# Sheet1.net
KiCad netlist of a schematic drawn in Altium Designer
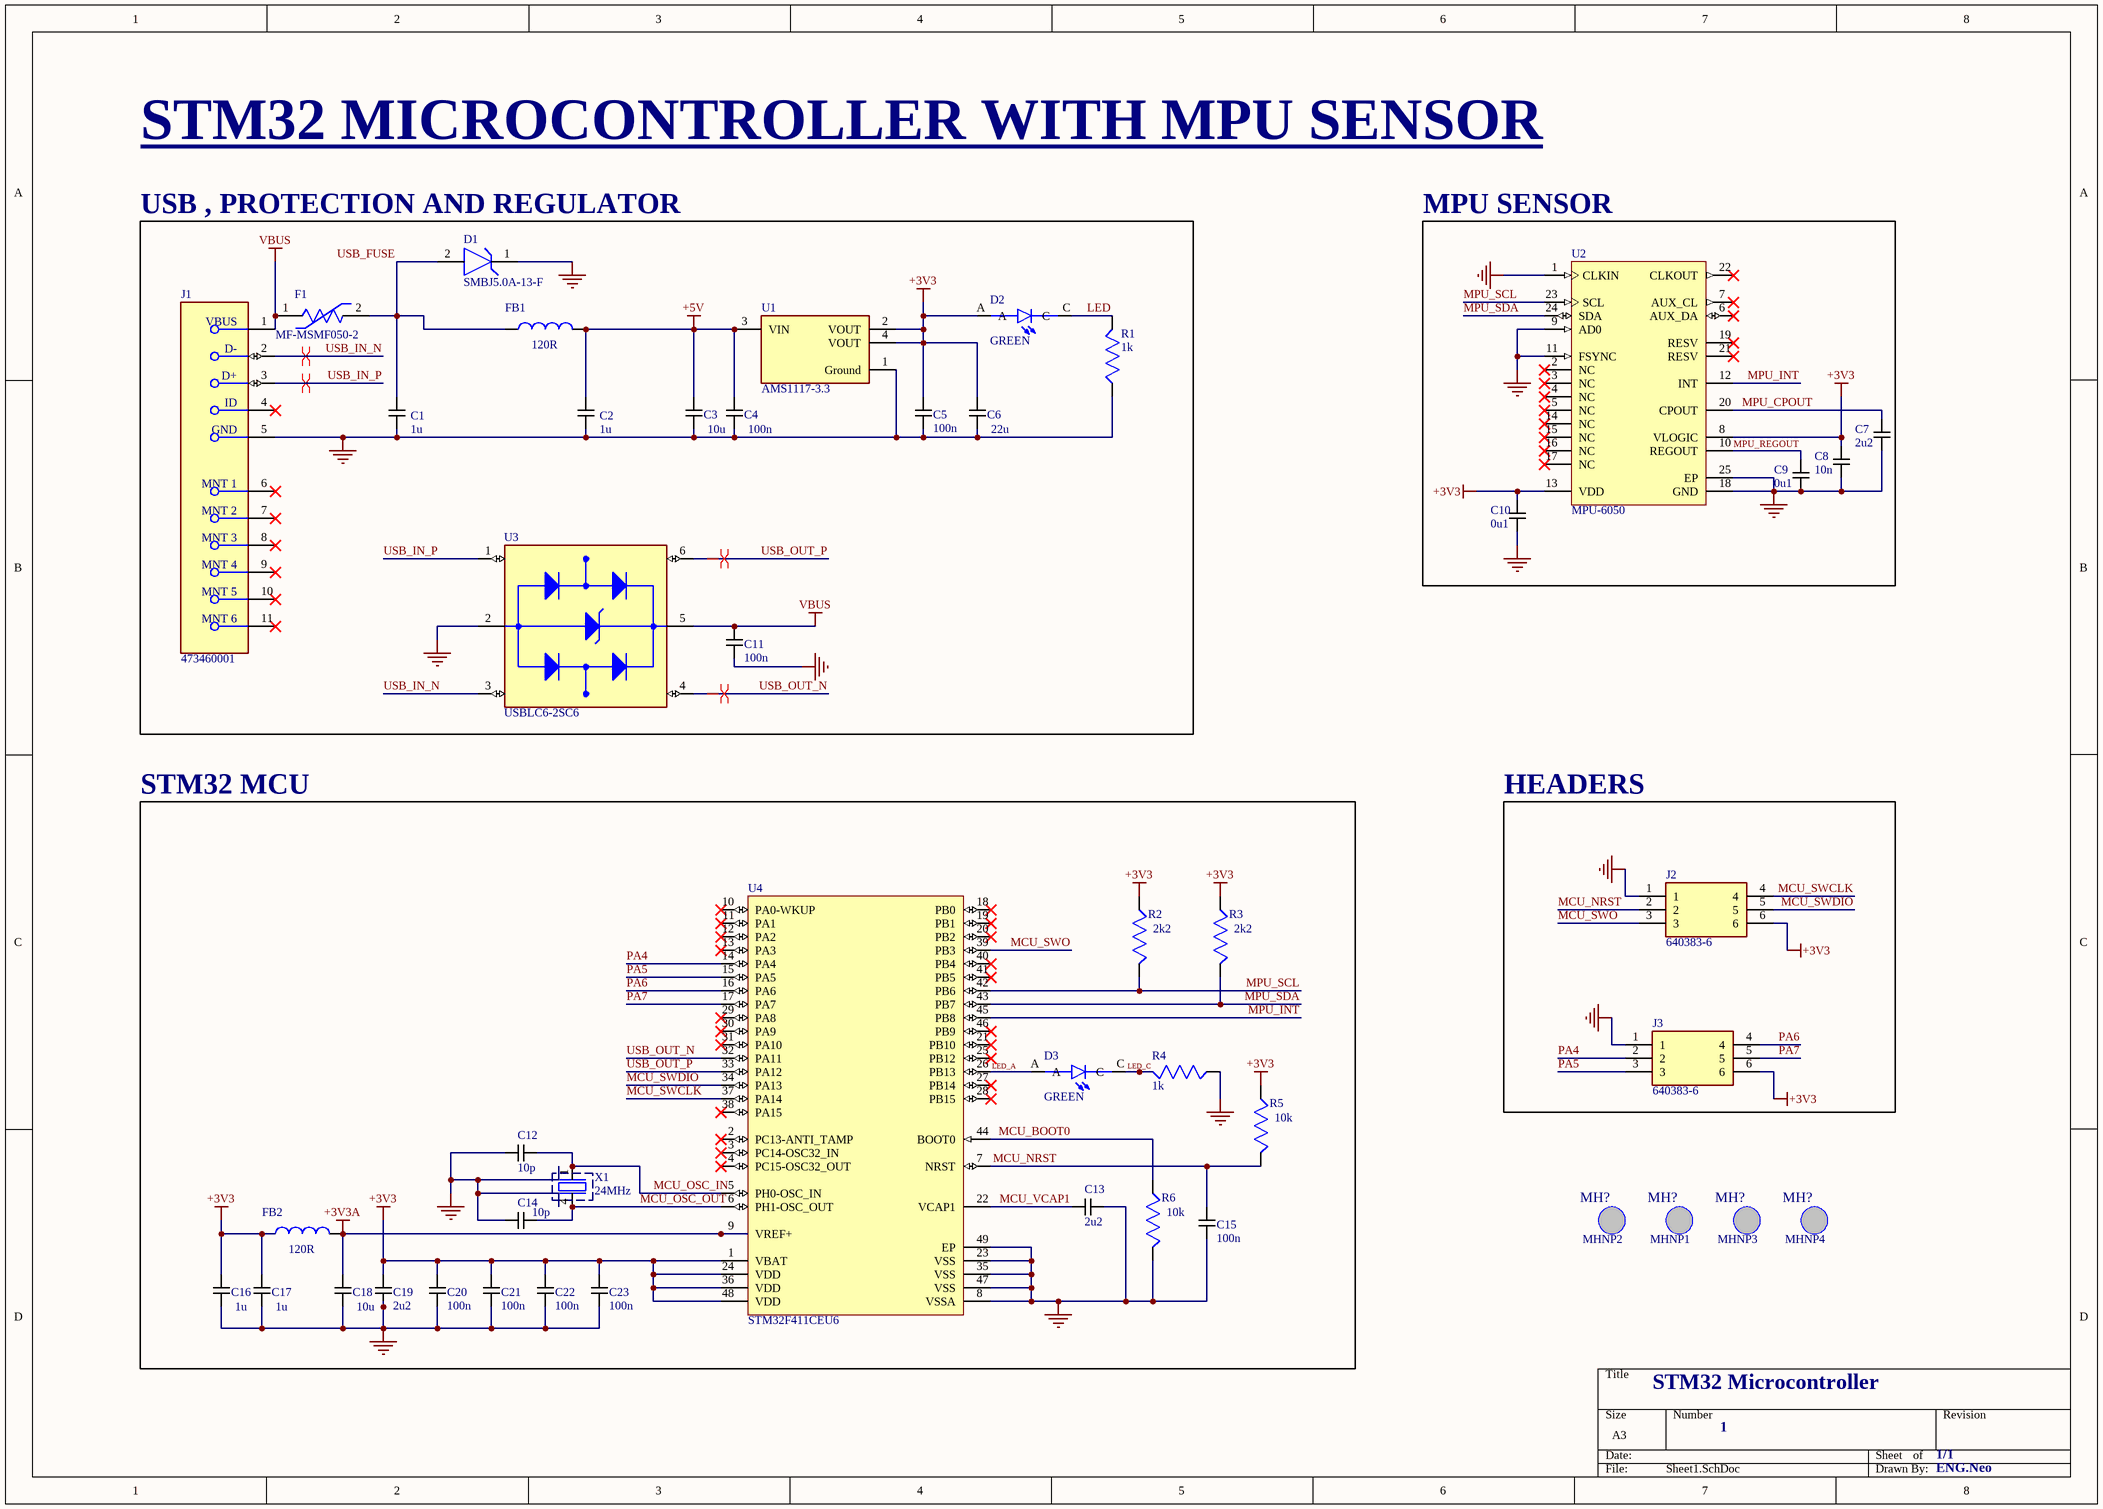
[diagram p0: Sheet1.SchDoc]

(export (version "E")
  (design (tool "Eeschema 10.0.6"))
  (components
    (comp (ref "C1")
      (value "100nF Ceramic Multilayer Capacitor_1")
      (footprint "CAPCP2012X09N")
      (description "AVX 0805 Standard 100nF Ceramic Multilayer Capacitor, 50 V dc X7R Dielectric ±10% SMD")
      (fields
        (field (name "MANUFACTURER") "AVX")
        (field (name "VOLTAGE") "50V")
        (field (name "CAPACITANCE") "1u")
        (field (name "CREATOR") "Ritesh Kanjee")
      )
      (libsource (lib "RS Components - Capacitors") (part "100nF Ceramic Multilayer Capacitor_1"))
    )
    (comp (ref "C2")
      (value "100nF Ceramic Multilayer Capacitor_1")
      (footprint "CAPCP2012X09N")
      (description "AVX 0805 Standard 100nF Ceramic Multilayer Capacitor, 50 V dc X7R Dielectric ±10% SMD")
      (fields
        (field (name "MANUFACTURER") "AVX")
        (field (name "VOLTAGE") "50V")
        (field (name "CAPACITANCE") "1u")
        (field (name "CREATOR") "Ritesh Kanjee")
      )
      (libsource (lib "RS Components - Capacitors") (part "100nF Ceramic Multilayer Capacitor_1"))
    )
    (comp (ref "C3")
      (value "100nF Ceramic Multilayer Capacitor_1")
      (footprint "CAPCP2012X09N")
      (description "AVX 0805 Standard 100nF Ceramic Multilayer Capacitor, 50 V dc X7R Dielectric ±10% SMD")
      (fields
        (field (name "MANUFACTURER") "AVX")
        (field (name "VOLTAGE") "50V")
        (field (name "CAPACITANCE") "10u")
        (field (name "CREATOR") "Ritesh Kanjee")
      )
      (libsource (lib "RS Components - Capacitors") (part "100nF Ceramic Multilayer Capacitor_1"))
    )
    (comp (ref "C4")
      (value "100nF Ceramic Multilayer Capacitor_1")
      (footprint "CAPCP2012X09N")
      (description "AVX 0805 Standard 100nF Ceramic Multilayer Capacitor, 50 V dc X7R Dielectric ±10% SMD")
      (fields
        (field (name "MANUFACTURER") "AVX")
        (field (name "VOLTAGE") "50V")
        (field (name "CAPACITANCE") "100n")
        (field (name "CREATOR") "Ritesh Kanjee")
      )
      (libsource (lib "RS Components - Capacitors") (part "100nF Ceramic Multilayer Capacitor_1"))
    )
    (comp (ref "C5")
      (value "100nF Ceramic Multilayer Capacitor_1")
      (footprint "CAPCP2012X09N")
      (description "AVX 0805 Standard 100nF Ceramic Multilayer Capacitor, 50 V dc X7R Dielectric ±10% SMD")
      (fields
        (field (name "MANUFACTURER") "AVX")
        (field (name "VOLTAGE") "50V")
        (field (name "CAPACITANCE") "100n")
        (field (name "CREATOR") "Ritesh Kanjee")
      )
      (libsource (lib "RS Components - Capacitors") (part "100nF Ceramic Multilayer Capacitor_1"))
    )
    (comp (ref "C6")
      (value "100nF Ceramic Multilayer Capacitor_1")
      (footprint "CAPCP2012X09N")
      (description "AVX 0805 Standard 100nF Ceramic Multilayer Capacitor, 50 V dc X7R Dielectric ±10% SMD")
      (fields
        (field (name "MANUFACTURER") "AVX")
        (field (name "VOLTAGE") "50V")
        (field (name "CAPACITANCE") "22u")
        (field (name "CREATOR") "Ritesh Kanjee")
      )
      (libsource (lib "RS Components - Capacitors") (part "100nF Ceramic Multilayer Capacitor_1"))
    )
    (comp (ref "C7")
      (value "100nF Ceramic Multilayer Capacitor_1")
      (footprint "CAPCP2012X09N")
      (description "AVX 0805 Standard 100nF Ceramic Multilayer Capacitor, 50 V dc X7R Dielectric ±10% SMD")
      (fields
        (field (name "MANUFACTURER") "AVX")
        (field (name "VOLTAGE") "50V")
        (field (name "CAPACITANCE") "2u2")
        (field (name "CREATOR") "Ritesh Kanjee")
      )
      (libsource (lib "RS Components - Capacitors") (part "100nF Ceramic Multilayer Capacitor_1"))
    )
    (comp (ref "C8")
      (value "100nF Ceramic Multilayer Capacitor_1")
      (footprint "CAPCP2012X09N")
      (description "AVX 0805 Standard 100nF Ceramic Multilayer Capacitor, 50 V dc X7R Dielectric ±10% SMD")
      (fields
        (field (name "MANUFACTURER") "AVX")
        (field (name "VOLTAGE") "50V")
        (field (name "CAPACITANCE") "10n")
        (field (name "CREATOR") "Ritesh Kanjee")
      )
      (libsource (lib "RS Components - Capacitors") (part "100nF Ceramic Multilayer Capacitor_1"))
    )
    (comp (ref "C9")
      (value "100nF Ceramic Multilayer Capacitor_1")
      (footprint "CAPCP2012X09N")
      (description "AVX 0805 Standard 100nF Ceramic Multilayer Capacitor, 50 V dc X7R Dielectric ±10% SMD")
      (fields
        (field (name "MANUFACTURER") "AVX")
        (field (name "VOLTAGE") "50V")
        (field (name "CAPACITANCE") "0u1")
        (field (name "CREATOR") "Ritesh Kanjee")
      )
      (libsource (lib "RS Components - Capacitors") (part "100nF Ceramic Multilayer Capacitor_1"))
    )
    (comp (ref "C10")
      (value "100nF Ceramic Multilayer Capacitor_1")
      (footprint "CAPCP2012X09N")
      (description "AVX 0805 Standard 100nF Ceramic Multilayer Capacitor, 50 V dc X7R Dielectric ±10% SMD")
      (fields
        (field (name "MANUFACTURER") "AVX")
        (field (name "VOLTAGE") "50V")
        (field (name "CAPACITANCE") "0u1")
        (field (name "CREATOR") "Ritesh Kanjee")
      )
      (libsource (lib "RS Components - Capacitors") (part "100nF Ceramic Multilayer Capacitor_1"))
    )
    (comp (ref "C11")
      (value "100nF Ceramic Multilayer Capacitor_1")
      (footprint "CAPCP2012X09N")
      (description "AVX 0805 Standard 100nF Ceramic Multilayer Capacitor, 50 V dc X7R Dielectric ±10% SMD")
      (fields
        (field (name "MANUFACTURER") "AVX")
        (field (name "VOLTAGE") "50V")
        (field (name "CAPACITANCE") "100n")
        (field (name "CREATOR") "Ritesh Kanjee")
      )
      (libsource (lib "RS Components - Capacitors") (part "100nF Ceramic Multilayer Capacitor_1"))
    )
    (comp (ref "C12")
      (value "100nF Ceramic Multilayer Capacitor_1")
      (footprint "CAPCP2012X09N")
      (description "AVX 0805 Standard 100nF Ceramic Multilayer Capacitor, 50 V dc X7R Dielectric ±10% SMD")
      (fields
        (field (name "MANUFACTURER") "AVX")
        (field (name "VOLTAGE") "50V")
        (field (name "CAPACITANCE") "10p")
        (field (name "CREATOR") "Ritesh Kanjee")
      )
      (libsource (lib "RS Components - Capacitors") (part "100nF Ceramic Multilayer Capacitor_1"))
    )
    (comp (ref "C13")
      (value "100nF Ceramic Multilayer Capacitor_1")
      (footprint "CAPCP2012X09N")
      (description "AVX 0805 Standard 100nF Ceramic Multilayer Capacitor, 50 V dc X7R Dielectric ±10% SMD")
      (fields
        (field (name "MANUFACTURER") "AVX")
        (field (name "VOLTAGE") "50V")
        (field (name "CAPACITANCE") "2u2")
        (field (name "CREATOR") "Ritesh Kanjee")
      )
      (libsource (lib "RS Components - Capacitors") (part "100nF Ceramic Multilayer Capacitor_1"))
    )
    (comp (ref "C14")
      (value "100nF Ceramic Multilayer Capacitor_1")
      (footprint "CAPCP2012X09N")
      (description "AVX 0805 Standard 100nF Ceramic Multilayer Capacitor, 50 V dc X7R Dielectric ±10% SMD")
      (fields
        (field (name "MANUFACTURER") "AVX")
        (field (name "VOLTAGE") "50V")
        (field (name "CAPACITANCE") "10p")
        (field (name "CREATOR") "Ritesh Kanjee")
      )
      (libsource (lib "RS Components - Capacitors") (part "100nF Ceramic Multilayer Capacitor_1"))
    )
    (comp (ref "C15")
      (value "100nF Ceramic Multilayer Capacitor_1")
      (footprint "CAPCP2012X09N")
      (description "AVX 0805 Standard 100nF Ceramic Multilayer Capacitor, 50 V dc X7R Dielectric ±10% SMD")
      (fields
        (field (name "MANUFACTURER") "AVX")
        (field (name "VOLTAGE") "50V")
        (field (name "CAPACITANCE") "100n")
        (field (name "CREATOR") "Ritesh Kanjee")
      )
      (libsource (lib "RS Components - Capacitors") (part "100nF Ceramic Multilayer Capacitor_1"))
    )
    (comp (ref "C16")
      (value "100nF Ceramic Multilayer Capacitor_1")
      (footprint "CAPCP2012X09N")
      (description "AVX 0805 Standard 100nF Ceramic Multilayer Capacitor, 50 V dc X7R Dielectric ±10% SMD")
      (fields
        (field (name "MANUFACTURER") "AVX")
        (field (name "VOLTAGE") "50V")
        (field (name "CAPACITANCE") "1u")
        (field (name "CREATOR") "Ritesh Kanjee")
      )
      (libsource (lib "RS Components - Capacitors") (part "100nF Ceramic Multilayer Capacitor_1"))
    )
    (comp (ref "C17")
      (value "100nF Ceramic Multilayer Capacitor_1")
      (footprint "CAPCP2012X09N")
      (description "AVX 0805 Standard 100nF Ceramic Multilayer Capacitor, 50 V dc X7R Dielectric ±10% SMD")
      (fields
        (field (name "MANUFACTURER") "AVX")
        (field (name "VOLTAGE") "50V")
        (field (name "CAPACITANCE") "1u")
        (field (name "CREATOR") "Ritesh Kanjee")
      )
      (libsource (lib "RS Components - Capacitors") (part "100nF Ceramic Multilayer Capacitor_1"))
    )
    (comp (ref "C18")
      (value "100nF Ceramic Multilayer Capacitor_1")
      (footprint "CAPCP2012X09N")
      (description "AVX 0805 Standard 100nF Ceramic Multilayer Capacitor, 50 V dc X7R Dielectric ±10% SMD")
      (fields
        (field (name "MANUFACTURER") "AVX")
        (field (name "VOLTAGE") "50V")
        (field (name "CAPACITANCE") "10u")
        (field (name "CREATOR") "Ritesh Kanjee")
      )
      (libsource (lib "RS Components - Capacitors") (part "100nF Ceramic Multilayer Capacitor_1"))
    )
    (comp (ref "C19")
      (value "100nF Ceramic Multilayer Capacitor_1")
      (footprint "CAPCP2012X09N")
      (description "AVX 0805 Standard 100nF Ceramic Multilayer Capacitor, 50 V dc X7R Dielectric ±10% SMD")
      (fields
        (field (name "MANUFACTURER") "AVX")
        (field (name "VOLTAGE") "50V")
        (field (name "CAPACITANCE") "2u2")
        (field (name "CREATOR") "Ritesh Kanjee")
      )
      (libsource (lib "RS Components - Capacitors") (part "100nF Ceramic Multilayer Capacitor_1"))
    )
    (comp (ref "C20")
      (value "100nF Ceramic Multilayer Capacitor_1")
      (footprint "CAPCP2012X09N")
      (description "AVX 0805 Standard 100nF Ceramic Multilayer Capacitor, 50 V dc X7R Dielectric ±10% SMD")
      (fields
        (field (name "MANUFACTURER") "AVX")
        (field (name "VOLTAGE") "50V")
        (field (name "CAPACITANCE") "100n")
        (field (name "CREATOR") "Ritesh Kanjee")
      )
      (libsource (lib "RS Components - Capacitors") (part "100nF Ceramic Multilayer Capacitor_1"))
    )
    (comp (ref "C21")
      (value "100nF Ceramic Multilayer Capacitor_1")
      (footprint "CAPCP2012X09N")
      (description "AVX 0805 Standard 100nF Ceramic Multilayer Capacitor, 50 V dc X7R Dielectric ±10% SMD")
      (fields
        (field (name "MANUFACTURER") "AVX")
        (field (name "VOLTAGE") "50V")
        (field (name "CAPACITANCE") "100n")
        (field (name "CREATOR") "Ritesh Kanjee")
      )
      (libsource (lib "RS Components - Capacitors") (part "100nF Ceramic Multilayer Capacitor_1"))
    )
    (comp (ref "C22")
      (value "100nF Ceramic Multilayer Capacitor_1")
      (footprint "CAPCP2012X09N")
      (description "AVX 0805 Standard 100nF Ceramic Multilayer Capacitor, 50 V dc X7R Dielectric ±10% SMD")
      (fields
        (field (name "MANUFACTURER") "AVX")
        (field (name "VOLTAGE") "50V")
        (field (name "CAPACITANCE") "100n")
        (field (name "CREATOR") "Ritesh Kanjee")
      )
      (libsource (lib "RS Components - Capacitors") (part "100nF Ceramic Multilayer Capacitor_1"))
    )
    (comp (ref "C23")
      (value "100nF Ceramic Multilayer Capacitor_1")
      (footprint "CAPCP2012X09N")
      (description "AVX 0805 Standard 100nF Ceramic Multilayer Capacitor, 50 V dc X7R Dielectric ±10% SMD")
      (fields
        (field (name "MANUFACTURER") "AVX")
        (field (name "VOLTAGE") "50V")
        (field (name "CAPACITANCE") "100n")
        (field (name "CREATOR") "Ritesh Kanjee")
      )
      (libsource (lib "RS Components - Capacitors") (part "100nF Ceramic Multilayer Capacitor_1"))
    )
    (comp (ref "D1")
      (value "SMBJ5.0A-13-F")
      (footprint "FP-SMB-MFG")
      (description "TVS DIODE 5V 9.2V SMB")
      (fields
        (field (name "OCTOPART") "https://octopart.com/smbj5.0a-13-f-diodes+inc.-350946")
        (field (name "MANUFACTURER") "Diodes Inc")
      )
      (libsource (lib "Components - 22.09.26 - 10.57") (part "CMP-12828-000017-1"))
    )
    (comp (ref "D2")
      (value "GREEN")
      (footprint "LEDC2012X70N")
      (description "LED Uni-Color Green 4-Pin Chip 0805 T/R")
      (fields (field (name "MP") "597-3305-607F"))
      (libsource (lib "597-3305-607F") (part "597-3305-607F"))
    )
    (comp (ref "D3")
      (value "GREEN")
      (footprint "LEDC2012X70N")
      (description "LED Uni-Color Green 4-Pin Chip 0805 T/R")
      (fields (field (name "MP") "597-3305-607F"))
      (libsource (lib "597-3305-607F") (part "597-3305-607F"))
    )
    (comp (ref "F1")
      (value "MF-MSMF050-2")
      (footprint "FP-MF-MSMF050-2-MFG")
      (description "PTC RESET FUSE 15V 500MA 1812")
      (fields
        (field (name "MANUFACTURER") "Bourns")
        (field (name "OCTOPART") "https://octopart.com/mf-msmf050-2-bourns-28047")
      )
      (libsource (lib "Components - 22.09.26 - 10.45") (part "CMP-2100-03653-2"))
    )
    (comp (ref "FB1")
      (value "120R")
      (footprint "WE-CBF HF_0603_HC")
      (description "Ferrite Bead (emi Suppression), 1.6X0.8X0.8MM (0603), 600O Impedance At 100 Mhz")
      (fields (field (name "TOLERANCE") "25%"))
      (libsource (lib "Components - 21.09.26 - 17.07") (part "CMP-0220-00101-3"))
    )
    (comp (ref "FB2")
      (value "120R")
      (footprint "WE-CBF HF_0603_HC")
      (description "Ferrite Bead (emi Suppression), 1.6X0.8X0.8MM (0603), 600O Impedance At 100 Mhz")
      (fields (field (name "TOLERANCE") "25%"))
      (libsource (lib "Components - 21.09.26 - 17.07") (part "CMP-0220-00101-3"))
    )
    (comp (ref "J1")
      (value "473460001")
      (footprint "FP-473460001-MFG")
      (description "CONN RCPT USB2.0 MICRO B SMD R/A")
      (fields
        (field (name "OCTOPART") "https://octopart.com/47346-0001-molex-7164928")
        (field (name "MANUFACTURER") "Molex")
      )
      (libsource (lib "Altium Content Vault") (part "53ae1f1d9b557310b43ca686e5bb76a"))
    )
    (comp (ref "J2")
      (value "640383-6")
      (footprint "TE_640383-6")
      (fields (field (name "MF") "TE Connectivity"))
      (libsource (lib "640383-6") (part "640383-6"))
    )
    (comp (ref "J3")
      (value "640383-6")
      (footprint "TE_640383-6")
      (fields (field (name "MF") "TE Connectivity"))
      (libsource (lib "640383-6") (part "640383-6"))
    )
    (comp (ref "MHNP1")
      (value "Mounting hole non plated 3.2mm")
      (footprint "MHNP3P2MM")
      (description "Mounting hole non plated 3.2mm drill hole")
      (libsource (lib "Integrated_Library1") (part "MHNP3P2MM"))
    )
    (comp (ref "MHNP2")
      (value "Mounting hole non plated 3.2mm")
      (footprint "MHNP3P2MM")
      (description "Mounting hole non plated 3.2mm drill hole")
      (libsource (lib "Integrated_Library1") (part "MHNP3P2MM"))
    )
    (comp (ref "MHNP3")
      (value "Mounting hole non plated 3.2mm")
      (footprint "MHNP3P2MM")
      (description "Mounting hole non plated 3.2mm drill hole")
      (libsource (lib "Integrated_Library1") (part "MHNP3P2MM"))
    )
    (comp (ref "MHNP4")
      (value "Mounting hole non plated 3.2mm")
      (footprint "MHNP3P2MM")
      (description "Mounting hole non plated 3.2mm drill hole")
      (libsource (lib "Integrated_Library1") (part "MHNP3P2MM"))
    )
    (comp (ref "R1")
      (value "1k")
      (footprint "RESC2012X60N")
      (fields (field (name "MP") "RC0805FR-102K7L"))
      (libsource (lib "RC0805FR-102K7L") (part "RC0805FR-102K7L"))
    )
    (comp (ref "R2")
      (value "2k2")
      (footprint "RESC2012X60N")
      (fields (field (name "MP") "RC0805FR-102K7L"))
      (libsource (lib "RC0805FR-102K7L") (part "RC0805FR-102K7L"))
    )
    (comp (ref "R3")
      (value "2k2")
      (footprint "RESC2012X60N")
      (fields (field (name "MP") "RC0805FR-102K7L"))
      (libsource (lib "RC0805FR-102K7L") (part "RC0805FR-102K7L"))
    )
    (comp (ref "R4")
      (value "1k")
      (footprint "RESC2012X60N")
      (fields (field (name "MP") "RC0805FR-102K7L"))
      (libsource (lib "RC0805FR-102K7L") (part "RC0805FR-102K7L"))
    )
    (comp (ref "R5")
      (value "10k")
      (footprint "RESC2012X60N")
      (fields (field (name "MP") "RC0805FR-102K7L"))
      (libsource (lib "RC0805FR-102K7L") (part "RC0805FR-102K7L"))
    )
    (comp (ref "R6")
      (value "10k")
      (footprint "RESC2012X60N")
      (fields (field (name "MP") "RC0805FR-102K7L"))
      (libsource (lib "RC0805FR-102K7L") (part "RC0805FR-102K7L"))
    )
    (comp (ref "U1")
      (value "AMS1117-3.3")
      (footprint "FP-AMS1117-IPC_C")
      (description "LDO Voltage Regulators 1A, 3.3V")
      (fields
        (field (name "OCTOPART") "https://octopart.com/ams1117-3.3-advanced+monolithic+systems-25899300")
        (field (name "MANUFACTURER") "Advanced Monolithic Systems")
      )
      (libsource (lib "Altium Content Vault") (part "8bdbb5f8e77002000e30dd2845d0354"))
    )
    (comp (ref "U2")
      (value "MPU-6050")
      (footprint "IS-QFN-24_V")
      (fields (field (name "MANUFACTURER") "InvenSense"))
      (libsource (lib "Components - 22.09.26 - 08.51") (part "CMP-1753-00002-2"))
    )
    (comp (ref "U3")
      (value "USBLC6-2SC6")
      (footprint "SOT95P280X145-6N")
      (description "17V Clamp 5A (8/20Âµs) Ipp Tvs Diode Surface Mount SOT-23-6")
      (fields (field (name "MF") "STMicroelectronics"))
      (libsource (lib "USBLC6-2SC6") (part "USBLC6-2SC6"))
    )
    (comp (ref "U4")
      (value "STM32F411CEU6")
      (footprint "STM-UFQFPN48_L")
      (libsource (lib "Components - 21.09.26 - 16.52") (part "CMP-0243-00165-1"))
    )
    (comp (ref "X1")
      (value "24MHz")
      (footprint "Aker S5C Crystal")
      (description "Aker S5C SMT Crystal")
      (fields
        (field (name "MANUFACTURER") "Aker")
        (field (name "MANUFACTURER PART #") "C5S-16.000-12-3030-X")
        (field (name "CREATOR") "R Kanjee")
      )
      (libsource (lib "Aker Crystals") (part "Aker  C5S-16.000-12-3030-X"))
    )
  )
  (nets
    (net (code "1") (name "+3V3") (class "Default")
      (node (ref "C10") (pin "2") (pinfunction "2_2") (pintype "passive"))
      (node (ref "C16") (pin "2") (pinfunction "2_2") (pintype "passive"))
      (node (ref "C17") (pin "2") (pinfunction "2_2") (pintype "passive"))
      (node (ref "C19") (pin "2") (pinfunction "2_2") (pintype "passive"))
      (node (ref "C20") (pin "2") (pinfunction "2_2") (pintype "passive"))
      (node (ref "C21") (pin "2") (pinfunction "2_2") (pintype "passive"))
      (node (ref "C22") (pin "2") (pinfunction "2_2") (pintype "passive"))
      (node (ref "C23") (pin "2") (pinfunction "2_2") (pintype "passive"))
      (node (ref "C5") (pin "1") (pinfunction "1_1") (pintype "passive"))
      (node (ref "C6") (pin "2") (pinfunction "2_2") (pintype "passive"))
      (node (ref "C8") (pin "2") (pinfunction "2_2") (pintype "passive"))
      (node (ref "D2") (pin "A") (pinfunction "A_A") (pintype "passive"))
      (node (ref "FB2") (pin "1") (pinfunction "1_1") (pintype "passive"))
      (node (ref "J2") (pin "6") (pinfunction "6_6") (pintype "passive"))
      (node (ref "J3") (pin "6") (pinfunction "6_6") (pintype "passive"))
      (node (ref "R2") (pin "2") (pinfunction "2_2") (pintype "passive"))
      (node (ref "R3") (pin "2") (pinfunction "2_2") (pintype "passive"))
      (node (ref "R5") (pin "2") (pinfunction "2_2") (pintype "passive"))
      (node (ref "U1") (pin "2") (pinfunction "VOUT_2") (pintype "passive"))
      (node (ref "U1") (pin "4") (pinfunction "VOUT_4") (pintype "passive"))
      (node (ref "U2") (pin "13") (pinfunction "VDD_13") (pintype "power_in"))
      (node (ref "U2") (pin "8") (pinfunction "VLOGIC_8") (pintype "power_in"))
      (node (ref "U4") (pin "1") (pinfunction "VBAT_1") (pintype "power_in"))
      (node (ref "U4") (pin "24") (pinfunction "VDD_24") (pintype "power_in"))
      (node (ref "U4") (pin "36") (pinfunction "VDD_36") (pintype "power_in"))
      (node (ref "U4") (pin "48") (pinfunction "VDD_48") (pintype "power_in"))
    )
    (net (code "2") (name "+3V3A") (class "Default")
      (node (ref "C18") (pin "2") (pinfunction "2_2") (pintype "passive"))
      (node (ref "FB2") (pin "2") (pinfunction "2_2") (pintype "passive"))
      (node (ref "U4") (pin "9") (pinfunction "VREF+_9") (pintype "power_in"))
    )
    (net (code "3") (name "+5V") (class "Default")
      (node (ref "C2") (pin "2") (pinfunction "2_2") (pintype "passive"))
      (node (ref "C3") (pin "2") (pinfunction "2_2") (pintype "passive"))
      (node (ref "C4") (pin "2") (pinfunction "2_2") (pintype "passive"))
      (node (ref "FB1") (pin "2") (pinfunction "2_2") (pintype "passive"))
      (node (ref "U1") (pin "3") (pinfunction "VIN_3") (pintype "power_in"))
    )
    (net (code "4") (name "/LED") (class "Default")
      (node (ref "D2") (pin "C") (pinfunction "C_C") (pintype "passive"))
      (node (ref "R1") (pin "1") (pinfunction "1_1") (pintype "passive"))
    )
    (net (code "5") (name "/LED_A") (class "Default")
      (node (ref "D3") (pin "A") (pinfunction "A_A") (pintype "passive"))
      (node (ref "U4") (pin "26") (pinfunction "PB13_26") (pintype "bidirectional"))
    )
    (net (code "6") (name "/LED_C") (class "Default")
      (node (ref "D3") (pin "C") (pinfunction "C_C") (pintype "passive"))
      (node (ref "R4") (pin "1") (pinfunction "1_1") (pintype "passive"))
    )
    (net (code "7") (name "/MCU_BOOT0") (class "Default")
      (node (ref "R6") (pin "2") (pinfunction "2_2") (pintype "passive"))
      (node (ref "U4") (pin "44") (pinfunction "BOOT0_44") (pintype "input"))
    )
    (net (code "8") (name "/MCU_NRST") (class "Default")
      (node (ref "C15") (pin "2") (pinfunction "2_2") (pintype "passive"))
      (node (ref "J2") (pin "2") (pinfunction "2_2") (pintype "passive"))
      (node (ref "R5") (pin "1") (pinfunction "1_1") (pintype "passive"))
      (node (ref "U4") (pin "7") (pinfunction "NRST_7") (pintype "bidirectional"))
    )
    (net (code "9") (name "/MCU_OSC_IN") (class "Default")
      (node (ref "C12") (pin "1") (pinfunction "1_1") (pintype "passive"))
      (node (ref "U4") (pin "5") (pinfunction "PH0-OSC_IN_5") (pintype "bidirectional"))
      (node (ref "X1") (pin "1") (pinfunction "1_1") (pintype "passive"))
    )
    (net (code "10") (name "/MCU_OSC_OUT") (class "Default")
      (node (ref "C14") (pin "1") (pinfunction "1_1") (pintype "passive"))
      (node (ref "U4") (pin "6") (pinfunction "PH1-OSC_OUT_6") (pintype "bidirectional"))
      (node (ref "X1") (pin "4") (pinfunction "4_4") (pintype "passive"))
    )
    (net (code "11") (name "/MCU_SWCLK") (class "Default")
      (node (ref "J2") (pin "4") (pinfunction "4_4") (pintype "passive"))
      (node (ref "U4") (pin "37") (pinfunction "PA14_37") (pintype "bidirectional"))
    )
    (net (code "12") (name "/MCU_SWDIO") (class "Default")
      (node (ref "J2") (pin "5") (pinfunction "5_5") (pintype "passive"))
      (node (ref "U4") (pin "34") (pinfunction "PA13_34") (pintype "bidirectional"))
    )
    (net (code "13") (name "/MCU_SWO") (class "Default")
      (node (ref "J2") (pin "3") (pinfunction "3_3") (pintype "passive"))
      (node (ref "U4") (pin "39") (pinfunction "PB3_39") (pintype "bidirectional"))
    )
    (net (code "14") (name "/MCU_VCAP1") (class "Default")
      (node (ref "C13") (pin "2") (pinfunction "2_2") (pintype "passive"))
      (node (ref "U4") (pin "22") (pinfunction "VCAP1_22") (pintype "passive"))
    )
    (net (code "15") (name "/MPU_CPOUT") (class "Default")
      (node (ref "C7") (pin "2") (pinfunction "2_2") (pintype "passive"))
      (node (ref "U2") (pin "20") (pinfunction "CPOUT_20") (pintype "passive"))
    )
    (net (code "16") (name "/MPU_INT") (class "Default")
      (node (ref "U2") (pin "12") (pinfunction "INT_12") (pintype "open_collector"))
      (node (ref "U4") (pin "45") (pinfunction "PB8_45") (pintype "bidirectional"))
    )
    (net (code "17") (name "/MPU_REGOUT") (class "Default")
      (node (ref "C9") (pin "2") (pinfunction "2_2") (pintype "passive"))
      (node (ref "U2") (pin "10") (pinfunction "REGOUT_10") (pintype "passive"))
    )
    (net (code "18") (name "/MPU_SCL") (class "Default")
      (node (ref "R2") (pin "1") (pinfunction "1_1") (pintype "passive"))
      (node (ref "U2") (pin "23") (pinfunction "SCL_23") (pintype "input"))
      (node (ref "U4") (pin "42") (pinfunction "PB6_42") (pintype "bidirectional"))
    )
    (net (code "19") (name "/MPU_SDA") (class "Default")
      (node (ref "R3") (pin "1") (pinfunction "1_1") (pintype "passive"))
      (node (ref "U2") (pin "24") (pinfunction "SDA_24") (pintype "bidirectional"))
      (node (ref "U4") (pin "43") (pinfunction "PB7_43") (pintype "bidirectional"))
    )
    (net (code "20") (name "/PA4") (class "Default")
      (node (ref "J3") (pin "2") (pinfunction "2_2") (pintype "passive"))
      (node (ref "U4") (pin "14") (pinfunction "PA4_14") (pintype "bidirectional"))
    )
    (net (code "21") (name "/PA5") (class "Default")
      (node (ref "J3") (pin "3") (pinfunction "3_3") (pintype "passive"))
      (node (ref "U4") (pin "15") (pinfunction "PA5_15") (pintype "bidirectional"))
    )
    (net (code "22") (name "/PA6") (class "Default")
      (node (ref "J3") (pin "4") (pinfunction "4_4") (pintype "passive"))
      (node (ref "U4") (pin "16") (pinfunction "PA6_16") (pintype "bidirectional"))
    )
    (net (code "23") (name "/PA7") (class "Default")
      (node (ref "J3") (pin "5") (pinfunction "5_5") (pintype "passive"))
      (node (ref "U4") (pin "17") (pinfunction "PA7_17") (pintype "bidirectional"))
    )
    (net (code "24") (name "/USB_FUSE") (class "Default")
      (node (ref "C1") (pin "2") (pinfunction "2_2") (pintype "passive"))
      (node (ref "D1") (pin "2") (pinfunction "A_2") (pintype "passive"))
      (node (ref "F1") (pin "2") (pinfunction "2_2") (pintype "passive"))
      (node (ref "FB1") (pin "1") (pinfunction "1_1") (pintype "passive"))
    )
    (net (code "25") (name "/USB_IN_N") (class "Default")
      (node (ref "J1") (pin "2") (pinfunction "D-_2") (pintype "bidirectional"))
      (node (ref "U3") (pin "3") (pinfunction "I/O2_IN_3") (pintype "bidirectional"))
    )
    (net (code "26") (name "/USB_IN_P") (class "Default")
      (node (ref "J1") (pin "3") (pinfunction "D+_3") (pintype "bidirectional"))
      (node (ref "U3") (pin "1") (pinfunction "I/O1_IN_1") (pintype "bidirectional"))
    )
    (net (code "27") (name "/USB_OUT_N") (class "Default")
      (node (ref "U3") (pin "4") (pinfunction "I/O2_OUT_4") (pintype "bidirectional"))
      (node (ref "U4") (pin "32") (pinfunction "PA11_32") (pintype "bidirectional"))
    )
    (net (code "28") (name "/USB_OUT_P") (class "Default")
      (node (ref "U3") (pin "6") (pinfunction "I/O1_OUT_6") (pintype "bidirectional"))
      (node (ref "U4") (pin "33") (pinfunction "PA12_33") (pintype "bidirectional"))
    )
    (net (code "29") (name "GND") (class "Default")
      (node (ref "C1") (pin "1") (pinfunction "1_1") (pintype "passive"))
      (node (ref "C10") (pin "1") (pinfunction "1_1") (pintype "passive"))
      (node (ref "C11") (pin "2") (pinfunction "2_2") (pintype "passive"))
      (node (ref "C12") (pin "2") (pinfunction "2_2") (pintype "passive"))
      (node (ref "C13") (pin "1") (pinfunction "1_1") (pintype "passive"))
      (node (ref "C14") (pin "2") (pinfunction "2_2") (pintype "passive"))
      (node (ref "C15") (pin "1") (pinfunction "1_1") (pintype "passive"))
      (node (ref "C16") (pin "1") (pinfunction "1_1") (pintype "passive"))
      (node (ref "C17") (pin "1") (pinfunction "1_1") (pintype "passive"))
      (node (ref "C18") (pin "1") (pinfunction "1_1") (pintype "passive"))
      (node (ref "C19") (pin "1") (pinfunction "1_1") (pintype "passive"))
      (node (ref "C2") (pin "1") (pinfunction "1_1") (pintype "passive"))
      (node (ref "C20") (pin "1") (pinfunction "1_1") (pintype "passive"))
      (node (ref "C21") (pin "1") (pinfunction "1_1") (pintype "passive"))
      (node (ref "C22") (pin "1") (pinfunction "1_1") (pintype "passive"))
      (node (ref "C23") (pin "1") (pinfunction "1_1") (pintype "passive"))
      (node (ref "C3") (pin "1") (pinfunction "1_1") (pintype "passive"))
      (node (ref "C4") (pin "1") (pinfunction "1_1") (pintype "passive"))
      (node (ref "C5") (pin "2") (pinfunction "2_2") (pintype "passive"))
      (node (ref "C6") (pin "1") (pinfunction "1_1") (pintype "passive"))
      (node (ref "C7") (pin "1") (pinfunction "1_1") (pintype "passive"))
      (node (ref "C8") (pin "1") (pinfunction "1_1") (pintype "passive"))
      (node (ref "C9") (pin "1") (pinfunction "1_1") (pintype "passive"))
      (node (ref "D1") (pin "1") (pinfunction "C_1") (pintype "passive"))
      (node (ref "J1") (pin "5") (pinfunction "GND_5") (pintype "power_in"))
      (node (ref "J2") (pin "1") (pinfunction "1_1") (pintype "passive"))
      (node (ref "J3") (pin "1") (pinfunction "1_1") (pintype "passive"))
      (node (ref "R1") (pin "2") (pinfunction "2_2") (pintype "passive"))
      (node (ref "R4") (pin "2") (pinfunction "2_2") (pintype "passive"))
      (node (ref "R6") (pin "1") (pinfunction "1_1") (pintype "passive"))
      (node (ref "U1") (pin "1") (pinfunction "Ground_1") (pintype "power_in"))
      (node (ref "U2") (pin "1") (pinfunction "CLKIN_1") (pintype "input"))
      (node (ref "U2") (pin "11") (pinfunction "FSYNC_11") (pintype "input"))
      (node (ref "U2") (pin "18") (pinfunction "GND_18") (pintype "power_in"))
      (node (ref "U2") (pin "25") (pinfunction "EP_25") (pintype "power_in"))
      (node (ref "U2") (pin "9") (pinfunction "AD0_9") (pintype "input"))
      (node (ref "U3") (pin "2") (pinfunction "GND_2") (pintype "power_in"))
      (node (ref "U4") (pin "23") (pinfunction "VSS_23") (pintype "power_in"))
      (node (ref "U4") (pin "35") (pinfunction "VSS_35") (pintype "power_in"))
      (node (ref "U4") (pin "47") (pinfunction "VSS_47") (pintype "power_in"))
      (node (ref "U4") (pin "49") (pinfunction "EP_49") (pintype "power_in"))
      (node (ref "U4") (pin "8") (pinfunction "VSSA_8") (pintype "power_in"))
      (node (ref "X1") (pin "2") (pinfunction "Gnd_2") (pintype "power_in"))
      (node (ref "X1") (pin "3") (pinfunction "Gnd_3") (pintype "power_in"))
    )
    (net (code "30") (name "VBUS") (class "Default")
      (node (ref "C11") (pin "1") (pinfunction "1_1") (pintype "passive"))
      (node (ref "F1") (pin "1") (pinfunction "1_1") (pintype "passive"))
      (node (ref "J1") (pin "1") (pinfunction "VBUS_1") (pintype "power_in"))
      (node (ref "U3") (pin "5") (pinfunction "VBUS_5") (pintype "power_in"))
    )
    (net (code "31") (name "unconnected-(J1-ID-Pad4)") (class "Default")
      (node (ref "J1") (pin "4") (pinfunction "ID_4") (pintype "passive+no_connect"))
    )
    (net (code "32") (name "unconnected-(J1-MNT_1-Pad6)") (class "Default")
      (node (ref "J1") (pin "6") (pinfunction "MNT_1_6") (pintype "passive+no_connect"))
    )
    (net (code "33") (name "unconnected-(J1-MNT_2-Pad7)") (class "Default")
      (node (ref "J1") (pin "7") (pinfunction "MNT_2_7") (pintype "passive+no_connect"))
    )
    (net (code "34") (name "unconnected-(J1-MNT_3-Pad8)") (class "Default")
      (node (ref "J1") (pin "8") (pinfunction "MNT_3_8") (pintype "passive+no_connect"))
    )
    (net (code "35") (name "unconnected-(J1-MNT_4-Pad9)") (class "Default")
      (node (ref "J1") (pin "9") (pinfunction "MNT_4_9") (pintype "passive+no_connect"))
    )
    (net (code "36") (name "unconnected-(J1-MNT_5-Pad10)") (class "Default")
      (node (ref "J1") (pin "10") (pinfunction "MNT_5_10") (pintype "passive+no_connect"))
    )
    (net (code "37") (name "unconnected-(J1-MNT_6-Pad11)") (class "Default")
      (node (ref "J1") (pin "11") (pinfunction "MNT_6_11") (pintype "passive+no_connect"))
    )
    (net (code "38") (name "unconnected-(U2-AUX_CL-Pad7)") (class "Default")
      (node (ref "U2") (pin "7") (pinfunction "AUX_CL_7") (pintype "output+no_connect"))
    )
    (net (code "39") (name "unconnected-(U2-AUX_DA-Pad6)") (class "Default")
      (node (ref "U2") (pin "6") (pinfunction "AUX_DA_6") (pintype "bidirectional+no_connect"))
    )
    (net (code "40") (name "unconnected-(U2-CLKOUT-Pad22)") (class "Default")
      (node (ref "U2") (pin "22") (pinfunction "CLKOUT_22") (pintype "output+no_connect"))
    )
    (net (code "41") (name "unconnected-(U2-NC-Pad2)") (class "Default")
      (node (ref "U2") (pin "2") (pinfunction "NC_2") (pintype "passive+no_connect"))
    )
    (net (code "42") (name "unconnected-(U2-NC-Pad3)") (class "Default")
      (node (ref "U2") (pin "3") (pinfunction "NC_3") (pintype "passive+no_connect"))
    )
    (net (code "43") (name "unconnected-(U2-NC-Pad4)") (class "Default")
      (node (ref "U2") (pin "4") (pinfunction "NC_4") (pintype "passive+no_connect"))
    )
    (net (code "44") (name "unconnected-(U2-NC-Pad5)") (class "Default")
      (node (ref "U2") (pin "5") (pinfunction "NC_5") (pintype "passive+no_connect"))
    )
    (net (code "45") (name "unconnected-(U2-NC-Pad14)") (class "Default")
      (node (ref "U2") (pin "14") (pinfunction "NC_14") (pintype "passive+no_connect"))
    )
    (net (code "46") (name "unconnected-(U2-NC-Pad15)") (class "Default")
      (node (ref "U2") (pin "15") (pinfunction "NC_15") (pintype "passive+no_connect"))
    )
    (net (code "47") (name "unconnected-(U2-NC-Pad16)") (class "Default")
      (node (ref "U2") (pin "16") (pinfunction "NC_16") (pintype "passive+no_connect"))
    )
    (net (code "48") (name "unconnected-(U2-NC-Pad17)") (class "Default")
      (node (ref "U2") (pin "17") (pinfunction "NC_17") (pintype "passive+no_connect"))
    )
    (net (code "49") (name "unconnected-(U2-RESV-Pad19)") (class "Default")
      (node (ref "U2") (pin "19") (pinfunction "RESV_19") (pintype "passive+no_connect"))
    )
    (net (code "50") (name "unconnected-(U2-RESV-Pad21)") (class "Default")
      (node (ref "U2") (pin "21") (pinfunction "RESV_21") (pintype "passive+no_connect"))
    )
    (net (code "51") (name "unconnected-(U4-PA0-WKUP-Pad10)") (class "Default")
      (node (ref "U4") (pin "10") (pinfunction "PA0-WKUP_10") (pintype "bidirectional+no_connect"))
    )
    (net (code "52") (name "unconnected-(U4-PA1-Pad11)") (class "Default")
      (node (ref "U4") (pin "11") (pinfunction "PA1_11") (pintype "bidirectional+no_connect"))
    )
    (net (code "53") (name "unconnected-(U4-PA2-Pad12)") (class "Default")
      (node (ref "U4") (pin "12") (pinfunction "PA2_12") (pintype "bidirectional+no_connect"))
    )
    (net (code "54") (name "unconnected-(U4-PA3-Pad13)") (class "Default")
      (node (ref "U4") (pin "13") (pinfunction "PA3_13") (pintype "bidirectional+no_connect"))
    )
    (net (code "55") (name "unconnected-(U4-PA8-Pad29)") (class "Default")
      (node (ref "U4") (pin "29") (pinfunction "PA8_29") (pintype "bidirectional+no_connect"))
    )
    (net (code "56") (name "unconnected-(U4-PA9-Pad30)") (class "Default")
      (node (ref "U4") (pin "30") (pinfunction "PA9_30") (pintype "bidirectional+no_connect"))
    )
    (net (code "57") (name "unconnected-(U4-PA10-Pad31)") (class "Default")
      (node (ref "U4") (pin "31") (pinfunction "PA10_31") (pintype "bidirectional+no_connect"))
    )
    (net (code "58") (name "unconnected-(U4-PA15-Pad38)") (class "Default")
      (node (ref "U4") (pin "38") (pinfunction "PA15_38") (pintype "bidirectional+no_connect"))
    )
    (net (code "59") (name "unconnected-(U4-PB0-Pad18)") (class "Default")
      (node (ref "U4") (pin "18") (pinfunction "PB0_18") (pintype "bidirectional+no_connect"))
    )
    (net (code "60") (name "unconnected-(U4-PB1-Pad19)") (class "Default")
      (node (ref "U4") (pin "19") (pinfunction "PB1_19") (pintype "bidirectional+no_connect"))
    )
    (net (code "61") (name "unconnected-(U4-PB2-Pad20)") (class "Default")
      (node (ref "U4") (pin "20") (pinfunction "PB2_20") (pintype "bidirectional+no_connect"))
    )
    (net (code "62") (name "unconnected-(U4-PB4-Pad40)") (class "Default")
      (node (ref "U4") (pin "40") (pinfunction "PB4_40") (pintype "bidirectional+no_connect"))
    )
    (net (code "63") (name "unconnected-(U4-PB5-Pad41)") (class "Default")
      (node (ref "U4") (pin "41") (pinfunction "PB5_41") (pintype "bidirectional+no_connect"))
    )
    (net (code "64") (name "unconnected-(U4-PB9-Pad46)") (class "Default")
      (node (ref "U4") (pin "46") (pinfunction "PB9_46") (pintype "bidirectional+no_connect"))
    )
    (net (code "65") (name "unconnected-(U4-PB10-Pad21)") (class "Default")
      (node (ref "U4") (pin "21") (pinfunction "PB10_21") (pintype "bidirectional+no_connect"))
    )
    (net (code "66") (name "unconnected-(U4-PB12-Pad25)") (class "Default")
      (node (ref "U4") (pin "25") (pinfunction "PB12_25") (pintype "bidirectional+no_connect"))
    )
    (net (code "67") (name "unconnected-(U4-PB14-Pad27)") (class "Default")
      (node (ref "U4") (pin "27") (pinfunction "PB14_27") (pintype "bidirectional+no_connect"))
    )
    (net (code "68") (name "unconnected-(U4-PB15-Pad28)") (class "Default")
      (node (ref "U4") (pin "28") (pinfunction "PB15_28") (pintype "bidirectional+no_connect"))
    )
    (net (code "69") (name "unconnected-(U4-PC13-ANTI_TAMP-Pad2)") (class "Default")
      (node (ref "U4") (pin "2") (pinfunction "PC13-ANTI_TAMP_2") (pintype "bidirectional+no_connect"))
    )
    (net (code "70") (name "unconnected-(U4-PC14-OSC32_IN-Pad3)") (class "Default")
      (node (ref "U4") (pin "3") (pinfunction "PC14-OSC32_IN_3") (pintype "bidirectional+no_connect"))
    )
    (net (code "71") (name "unconnected-(U4-PC15-OSC32_OUT-Pad4)") (class "Default")
      (node (ref "U4") (pin "4") (pinfunction "PC15-OSC32_OUT_4") (pintype "bidirectional+no_connect"))
    )
  )
)
